# DIGITAL_OUTPUT.net
KiCad netlist of a schematic drawn in Altium Designer
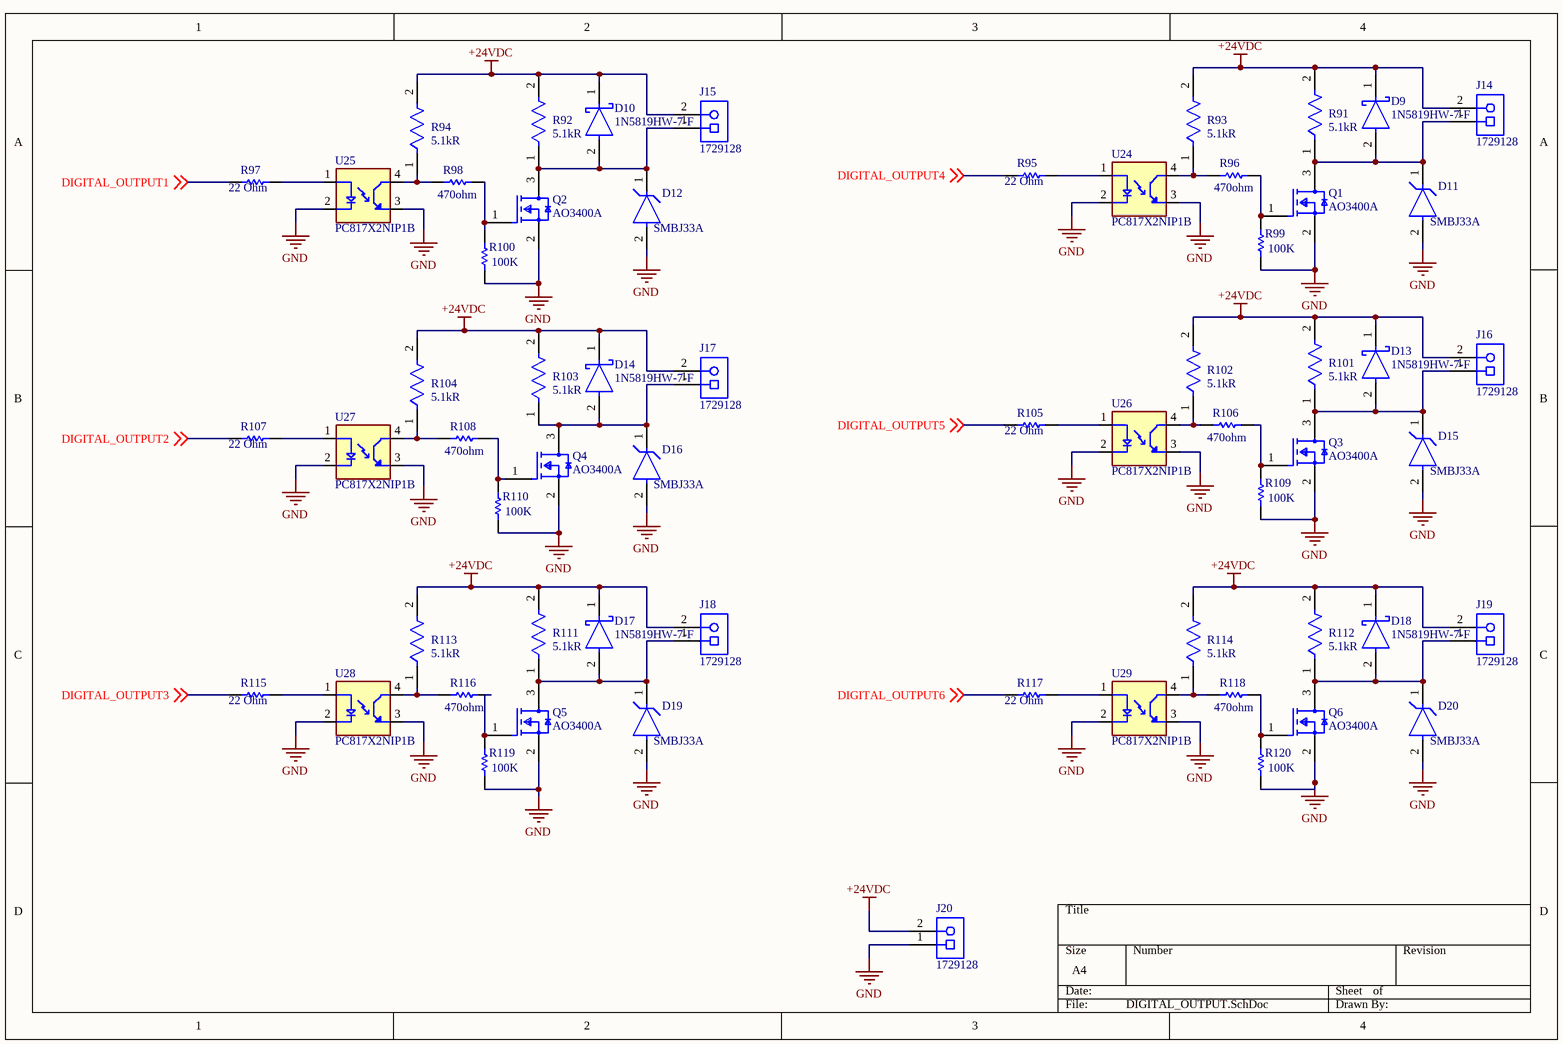
[diagram p0: DIGITAL_OUTPUT.SchDoc]

(export (version "E")
  (design (tool "Eeschema 10.0.6"))
  (components
    (comp (ref "D9")
      (value "1N5819HW-7-F")
      (footprint "FP-SOD123-IPC_A")
      (description "DIODE SCHOTTKY 40V 1A SOD123")
      (libsource (lib "Altium Content Vault") (part "1d6ec82d83fb6aee721767c19dac4b9"))
    )
    (comp (ref "D10")
      (value "1N5819HW-7-F")
      (footprint "FP-SOD123-IPC_A")
      (description "DIODE SCHOTTKY 40V 1A SOD123")
      (libsource (lib "Altium Content Vault") (part "1d6ec82d83fb6aee721767c19dac4b9"))
    )
    (comp (ref "D11")
      (value "SMBJ33A")
      (footprint "FP-SMBJ-MFG")
      (description "TVS DIODE 33V 53.3V DO214AA")
      (fields
        (field (name "MANUFACTURER") "Littelfuse Inc")
        (field (name "OCTOPART") "https://octopart.com/smbj33a-littelfuse-350829")
      )
      (libsource (lib "Altium Content Vault") (part "f813f71cba58e380607f5dd3caf9714"))
    )
    (comp (ref "D12")
      (value "SMBJ33A")
      (footprint "FP-SMBJ-MFG")
      (description "TVS DIODE 33V 53.3V DO214AA")
      (fields
        (field (name "MANUFACTURER") "Littelfuse Inc")
        (field (name "OCTOPART") "https://octopart.com/smbj33a-littelfuse-350829")
      )
      (libsource (lib "Altium Content Vault") (part "f813f71cba58e380607f5dd3caf9714"))
    )
    (comp (ref "D13")
      (value "1N5819HW-7-F")
      (footprint "FP-SOD123-IPC_A")
      (description "DIODE SCHOTTKY 40V 1A SOD123")
      (libsource (lib "Altium Content Vault") (part "1d6ec82d83fb6aee721767c19dac4b9"))
    )
    (comp (ref "D14")
      (value "1N5819HW-7-F")
      (footprint "FP-SOD123-IPC_A")
      (description "DIODE SCHOTTKY 40V 1A SOD123")
      (libsource (lib "Altium Content Vault") (part "1d6ec82d83fb6aee721767c19dac4b9"))
    )
    (comp (ref "D15")
      (value "SMBJ33A")
      (footprint "FP-SMBJ-MFG")
      (description "TVS DIODE 33V 53.3V DO214AA")
      (fields
        (field (name "MANUFACTURER") "Littelfuse Inc")
        (field (name "OCTOPART") "https://octopart.com/smbj33a-littelfuse-350829")
      )
      (libsource (lib "Altium Content Vault") (part "f813f71cba58e380607f5dd3caf9714"))
    )
    (comp (ref "D16")
      (value "SMBJ33A")
      (footprint "FP-SMBJ-MFG")
      (description "TVS DIODE 33V 53.3V DO214AA")
      (fields
        (field (name "MANUFACTURER") "Littelfuse Inc")
        (field (name "OCTOPART") "https://octopart.com/smbj33a-littelfuse-350829")
      )
      (libsource (lib "Altium Content Vault") (part "f813f71cba58e380607f5dd3caf9714"))
    )
    (comp (ref "D17")
      (value "1N5819HW-7-F")
      (footprint "FP-SOD123-IPC_A")
      (description "DIODE SCHOTTKY 40V 1A SOD123")
      (libsource (lib "Altium Content Vault") (part "1d6ec82d83fb6aee721767c19dac4b9"))
    )
    (comp (ref "D18")
      (value "1N5819HW-7-F")
      (footprint "FP-SOD123-IPC_A")
      (description "DIODE SCHOTTKY 40V 1A SOD123")
      (libsource (lib "Altium Content Vault") (part "1d6ec82d83fb6aee721767c19dac4b9"))
    )
    (comp (ref "D19")
      (value "SMBJ33A")
      (footprint "FP-SMBJ-MFG")
      (description "TVS DIODE 33V 53.3V DO214AA")
      (fields
        (field (name "MANUFACTURER") "Littelfuse Inc")
        (field (name "OCTOPART") "https://octopart.com/smbj33a-littelfuse-350829")
      )
      (libsource (lib "Altium Content Vault") (part "f813f71cba58e380607f5dd3caf9714"))
    )
    (comp (ref "D20")
      (value "SMBJ33A")
      (footprint "FP-SMBJ-MFG")
      (description "TVS DIODE 33V 53.3V DO214AA")
      (fields
        (field (name "MANUFACTURER") "Littelfuse Inc")
        (field (name "OCTOPART") "https://octopart.com/smbj33a-littelfuse-350829")
      )
      (libsource (lib "Altium Content Vault") (part "f813f71cba58e380607f5dd3caf9714"))
    )
    (comp (ref "J14")
      (value "1729128")
      (footprint "PHOE-1729128-2_V")
      (description "PCB Terminal Block, 13.5 A, 400 V, 2-Pin THD, RoHS, Bulk")
      (fields (field (name "MANUFACTURER") "Phoenix Contact"))
      (libsource (lib "Altium Content Vault") (part "CN-2P-F-R2"))
    )
    (comp (ref "J15")
      (value "1729128")
      (footprint "PHOE-1729128-2_V")
      (description "PCB Terminal Block, 13.5 A, 400 V, 2-Pin THD, RoHS, Bulk")
      (fields (field (name "MANUFACTURER") "Phoenix Contact"))
      (libsource (lib "Altium Content Vault") (part "CN-2P-F-R2"))
    )
    (comp (ref "J16")
      (value "1729128")
      (footprint "PHOE-1729128-2_V")
      (description "PCB Terminal Block, 13.5 A, 400 V, 2-Pin THD, RoHS, Bulk")
      (fields (field (name "MANUFACTURER") "Phoenix Contact"))
      (libsource (lib "Altium Content Vault") (part "CN-2P-F-R2"))
    )
    (comp (ref "J17")
      (value "1729128")
      (footprint "PHOE-1729128-2_V")
      (description "PCB Terminal Block, 13.5 A, 400 V, 2-Pin THD, RoHS, Bulk")
      (fields (field (name "MANUFACTURER") "Phoenix Contact"))
      (libsource (lib "Altium Content Vault") (part "CN-2P-F-R2"))
    )
    (comp (ref "J18")
      (value "1729128")
      (footprint "PHOE-1729128-2_V")
      (description "PCB Terminal Block, 13.5 A, 400 V, 2-Pin THD, RoHS, Bulk")
      (fields (field (name "MANUFACTURER") "Phoenix Contact"))
      (libsource (lib "Altium Content Vault") (part "CN-2P-F-R2"))
    )
    (comp (ref "J19")
      (value "1729128")
      (footprint "PHOE-1729128-2_V")
      (description "PCB Terminal Block, 13.5 A, 400 V, 2-Pin THD, RoHS, Bulk")
      (fields (field (name "MANUFACTURER") "Phoenix Contact"))
      (libsource (lib "Altium Content Vault") (part "CN-2P-F-R2"))
    )
    (comp (ref "J20")
      (value "1729128")
      (footprint "PHOE-1729128-2_V")
      (description "PCB Terminal Block, 13.5 A, 400 V, 2-Pin THD, RoHS, Bulk")
      (fields (field (name "MANUFACTURER") "Phoenix Contact"))
      (libsource (lib "Altium Content Vault") (part "CN-2P-F-R2"))
    )
    (comp (ref "Q1")
      (value "AO3400A")
      (footprint "FP-SOT23-MFG")
      (description "MOSFET N-CH 30V 5.7A SOT23")
      (libsource (lib "Altium Content Vault") (part "0a9ea7c96deaaede766a5b531c28de0"))
    )
    (comp (ref "Q2")
      (value "AO3400A")
      (footprint "FP-SOT23-MFG")
      (description "MOSFET N-CH 30V 5.7A SOT23")
      (libsource (lib "Altium Content Vault") (part "0a9ea7c96deaaede766a5b531c28de0"))
    )
    (comp (ref "Q3")
      (value "AO3400A")
      (footprint "FP-SOT23-MFG")
      (description "MOSFET N-CH 30V 5.7A SOT23")
      (libsource (lib "Altium Content Vault") (part "0a9ea7c96deaaede766a5b531c28de0"))
    )
    (comp (ref "Q4")
      (value "AO3400A")
      (footprint "FP-SOT23-MFG")
      (description "MOSFET N-CH 30V 5.7A SOT23")
      (libsource (lib "Altium Content Vault") (part "0a9ea7c96deaaede766a5b531c28de0"))
    )
    (comp (ref "Q5")
      (value "AO3400A")
      (footprint "FP-SOT23-MFG")
      (description "MOSFET N-CH 30V 5.7A SOT23")
      (libsource (lib "Altium Content Vault") (part "0a9ea7c96deaaede766a5b531c28de0"))
    )
    (comp (ref "Q6")
      (value "AO3400A")
      (footprint "FP-SOT23-MFG")
      (description "MOSFET N-CH 30V 5.7A SOT23")
      (libsource (lib "Altium Content Vault") (part "0a9ea7c96deaaede766a5b531c28de0"))
    )
    (comp (ref "R91")
      (value "CRCW06035K10FKEA")
      (footprint "FP-CRCW0603-e3-IPC_C")
      (description "RES Thick Film, 5.1kΩ, 1%, 0.1W, 100ppm/°C, 0603")
      (fields (field (name "TOLERANCE") "1%") (field (name "RESISTANCE") "5.1kR"))
      (libsource (lib "Altium Content Vault") (part "1029c3af85768c4190bb7ad29bc67b5"))
    )
    (comp (ref "R92")
      (value "CRCW06035K10FKEA")
      (footprint "FP-CRCW0603-e3-IPC_C")
      (description "RES Thick Film, 5.1kΩ, 1%, 0.1W, 100ppm/°C, 0603")
      (fields (field (name "TOLERANCE") "1%") (field (name "RESISTANCE") "5.1kR"))
      (libsource (lib "Altium Content Vault") (part "1029c3af85768c4190bb7ad29bc67b5"))
    )
    (comp (ref "R93")
      (value "CRCW06035K10FKEA")
      (footprint "FP-CRCW0603-e3-IPC_C")
      (description "RES Thick Film, 5.1kΩ, 1%, 0.1W, 100ppm/°C, 0603")
      (fields (field (name "TOLERANCE") "1%") (field (name "RESISTANCE") "5.1kR"))
      (libsource (lib "Altium Content Vault") (part "1029c3af85768c4190bb7ad29bc67b5"))
    )
    (comp (ref "R94")
      (value "CRCW06035K10FKEA")
      (footprint "FP-CRCW0603-e3-IPC_C")
      (description "RES Thick Film, 5.1kΩ, 1%, 0.1W, 100ppm/°C, 0603")
      (fields (field (name "TOLERANCE") "1%") (field (name "RESISTANCE") "5.1kR"))
      (libsource (lib "Altium Content Vault") (part "1029c3af85768c4190bb7ad29bc67b5"))
    )
    (comp (ref "R95")
      (value "ERJ-3EKF2200V")
      (footprint "RESC1608X55X30LL15T15")
      (description "Chip Resistor, 220 Ohm, +/- 1%, 0.1 W, -55 to 155 degC, 0603 (1608 Metric), RoHS, Tape and Reel")
      (fields (field (name "RESISTANCE") "22 Ohm") (field (name "TOLERANCE") "1%"))
      (libsource (lib "Altium Content Vault") (part "RES-2"))
    )
    (comp (ref "R96")
      (value "RC0805FR-07470RL")
      (footprint "RESC2013X60X35LL10T20")
      (description "Chip Resistor, 470 Ohm, +/- 1%, 125 mW, -55 to 155 degC, 0805 (2012 Metric), RoHS, Tape and Reel")
      (fields (field (name "MANUFACTURER") "Yageo") (field (name "RESISTANCE") "470ohm"))
      (libsource (lib "Altium Content Vault") (part "RES-2"))
    )
    (comp (ref "R97")
      (value "ERJ-3EKF2200V")
      (footprint "RESC1608X55X30LL15T15")
      (description "Chip Resistor, 220 Ohm, +/- 1%, 0.1 W, -55 to 155 degC, 0603 (1608 Metric), RoHS, Tape and Reel")
      (fields (field (name "RESISTANCE") "22 Ohm") (field (name "TOLERANCE") "1%"))
      (libsource (lib "Altium Content Vault") (part "RES-2"))
    )
    (comp (ref "R98")
      (value "RC0805FR-07470RL")
      (footprint "RESC2013X60X35LL10T20")
      (description "Chip Resistor, 470 Ohm, +/- 1%, 125 mW, -55 to 155 degC, 0805 (2012 Metric), RoHS, Tape and Reel")
      (fields (field (name "MANUFACTURER") "Yageo") (field (name "RESISTANCE") "470ohm"))
      (libsource (lib "Altium Content Vault") (part "RES-2"))
    )
    (comp (ref "R99")
      (value "100K")
      (footprint "RESC2013X50X30ML20T20")
      (fields (field (name "MANUFACTURER") "Vishay Dale") (field (name "PART NUMBER") "CRCW0805100KJNEA"))
      (libsource (lib "Altium Content Vault") (part "RES"))
    )
    (comp (ref "R100")
      (value "100K")
      (footprint "RESC2013X50X30ML20T20")
      (fields (field (name "MANUFACTURER") "Vishay Dale") (field (name "PART NUMBER") "CRCW0805100KJNEA"))
      (libsource (lib "Altium Content Vault") (part "RES"))
    )
    (comp (ref "R101")
      (value "CRCW06035K10FKEA")
      (footprint "FP-CRCW0603-e3-IPC_C")
      (description "RES Thick Film, 5.1kΩ, 1%, 0.1W, 100ppm/°C, 0603")
      (fields (field (name "TOLERANCE") "1%") (field (name "RESISTANCE") "5.1kR"))
      (libsource (lib "Altium Content Vault") (part "1029c3af85768c4190bb7ad29bc67b5"))
    )
    (comp (ref "R102")
      (value "CRCW06035K10FKEA")
      (footprint "FP-CRCW0603-e3-IPC_C")
      (description "RES Thick Film, 5.1kΩ, 1%, 0.1W, 100ppm/°C, 0603")
      (fields (field (name "TOLERANCE") "1%") (field (name "RESISTANCE") "5.1kR"))
      (libsource (lib "Altium Content Vault") (part "1029c3af85768c4190bb7ad29bc67b5"))
    )
    (comp (ref "R103")
      (value "CRCW06035K10FKEA")
      (footprint "FP-CRCW0603-e3-IPC_C")
      (description "RES Thick Film, 5.1kΩ, 1%, 0.1W, 100ppm/°C, 0603")
      (fields (field (name "TOLERANCE") "1%") (field (name "RESISTANCE") "5.1kR"))
      (libsource (lib "Altium Content Vault") (part "1029c3af85768c4190bb7ad29bc67b5"))
    )
    (comp (ref "R104")
      (value "CRCW06035K10FKEA")
      (footprint "FP-CRCW0603-e3-IPC_C")
      (description "RES Thick Film, 5.1kΩ, 1%, 0.1W, 100ppm/°C, 0603")
      (fields (field (name "TOLERANCE") "1%") (field (name "RESISTANCE") "5.1kR"))
      (libsource (lib "Altium Content Vault") (part "1029c3af85768c4190bb7ad29bc67b5"))
    )
    (comp (ref "R105")
      (value "ERJ-3EKF2200V")
      (footprint "RESC1608X55X30LL15T15")
      (description "Chip Resistor, 220 Ohm, +/- 1%, 0.1 W, -55 to 155 degC, 0603 (1608 Metric), RoHS, Tape and Reel")
      (fields (field (name "RESISTANCE") "22 Ohm") (field (name "TOLERANCE") "1%"))
      (libsource (lib "Altium Content Vault") (part "RES-2"))
    )
    (comp (ref "R106")
      (value "RC0805FR-07470RL")
      (footprint "RESC2013X60X35LL10T20")
      (description "Chip Resistor, 470 Ohm, +/- 1%, 125 mW, -55 to 155 degC, 0805 (2012 Metric), RoHS, Tape and Reel")
      (fields (field (name "MANUFACTURER") "Yageo") (field (name "RESISTANCE") "470ohm"))
      (libsource (lib "Altium Content Vault") (part "RES-2"))
    )
    (comp (ref "R107")
      (value "ERJ-3EKF2200V")
      (footprint "RESC1608X55X30LL15T15")
      (description "Chip Resistor, 220 Ohm, +/- 1%, 0.1 W, -55 to 155 degC, 0603 (1608 Metric), RoHS, Tape and Reel")
      (fields (field (name "RESISTANCE") "22 Ohm") (field (name "TOLERANCE") "1%"))
      (libsource (lib "Altium Content Vault") (part "RES-2"))
    )
    (comp (ref "R108")
      (value "RC0805FR-07470RL")
      (footprint "RESC2013X60X35LL10T20")
      (description "Chip Resistor, 470 Ohm, +/- 1%, 125 mW, -55 to 155 degC, 0805 (2012 Metric), RoHS, Tape and Reel")
      (fields (field (name "MANUFACTURER") "Yageo") (field (name "RESISTANCE") "470ohm"))
      (libsource (lib "Altium Content Vault") (part "RES-2"))
    )
    (comp (ref "R109")
      (value "100K")
      (footprint "RESC2013X50X30ML20T20")
      (fields (field (name "MANUFACTURER") "Vishay Dale") (field (name "PART NUMBER") "CRCW0805100KJNEA"))
      (libsource (lib "Altium Content Vault") (part "RES"))
    )
    (comp (ref "R110")
      (value "100K")
      (footprint "RESC2013X50X30ML20T20")
      (fields (field (name "MANUFACTURER") "Vishay Dale") (field (name "PART NUMBER") "CRCW0805100KJNEA"))
      (libsource (lib "Altium Content Vault") (part "RES"))
    )
    (comp (ref "R111")
      (value "CRCW06035K10FKEA")
      (footprint "FP-CRCW0603-e3-IPC_C")
      (description "RES Thick Film, 5.1kΩ, 1%, 0.1W, 100ppm/°C, 0603")
      (fields (field (name "TOLERANCE") "1%") (field (name "RESISTANCE") "5.1kR"))
      (libsource (lib "Altium Content Vault") (part "1029c3af85768c4190bb7ad29bc67b5"))
    )
    (comp (ref "R112")
      (value "CRCW06035K10FKEA")
      (footprint "FP-CRCW0603-e3-IPC_C")
      (description "RES Thick Film, 5.1kΩ, 1%, 0.1W, 100ppm/°C, 0603")
      (fields (field (name "TOLERANCE") "1%") (field (name "RESISTANCE") "5.1kR"))
      (libsource (lib "Altium Content Vault") (part "1029c3af85768c4190bb7ad29bc67b5"))
    )
    (comp (ref "R113")
      (value "CRCW06035K10FKEA")
      (footprint "FP-CRCW0603-e3-IPC_C")
      (description "RES Thick Film, 5.1kΩ, 1%, 0.1W, 100ppm/°C, 0603")
      (fields (field (name "TOLERANCE") "1%") (field (name "RESISTANCE") "5.1kR"))
      (libsource (lib "Altium Content Vault") (part "1029c3af85768c4190bb7ad29bc67b5"))
    )
    (comp (ref "R114")
      (value "CRCW06035K10FKEA")
      (footprint "FP-CRCW0603-e3-IPC_C")
      (description "RES Thick Film, 5.1kΩ, 1%, 0.1W, 100ppm/°C, 0603")
      (fields (field (name "TOLERANCE") "1%") (field (name "RESISTANCE") "5.1kR"))
      (libsource (lib "Altium Content Vault") (part "1029c3af85768c4190bb7ad29bc67b5"))
    )
    (comp (ref "R115")
      (value "ERJ-3EKF2200V")
      (footprint "RESC1608X55X30LL15T15")
      (description "Chip Resistor, 220 Ohm, +/- 1%, 0.1 W, -55 to 155 degC, 0603 (1608 Metric), RoHS, Tape and Reel")
      (fields (field (name "RESISTANCE") "22 Ohm") (field (name "TOLERANCE") "1%"))
      (libsource (lib "Altium Content Vault") (part "RES-2"))
    )
    (comp (ref "R116")
      (value "RC0805FR-07470RL")
      (footprint "RESC2013X60X35LL10T20")
      (description "Chip Resistor, 470 Ohm, +/- 1%, 125 mW, -55 to 155 degC, 0805 (2012 Metric), RoHS, Tape and Reel")
      (fields (field (name "MANUFACTURER") "Yageo") (field (name "RESISTANCE") "470ohm"))
      (libsource (lib "Altium Content Vault") (part "RES-2"))
    )
    (comp (ref "R117")
      (value "ERJ-3EKF2200V")
      (footprint "RESC1608X55X30LL15T15")
      (description "Chip Resistor, 220 Ohm, +/- 1%, 0.1 W, -55 to 155 degC, 0603 (1608 Metric), RoHS, Tape and Reel")
      (fields (field (name "RESISTANCE") "22 Ohm") (field (name "TOLERANCE") "1%"))
      (libsource (lib "Altium Content Vault") (part "RES-2"))
    )
    (comp (ref "R118")
      (value "RC0805FR-07470RL")
      (footprint "RESC2013X60X35LL10T20")
      (description "Chip Resistor, 470 Ohm, +/- 1%, 125 mW, -55 to 155 degC, 0805 (2012 Metric), RoHS, Tape and Reel")
      (fields (field (name "MANUFACTURER") "Yageo") (field (name "RESISTANCE") "470ohm"))
      (libsource (lib "Altium Content Vault") (part "RES-2"))
    )
    (comp (ref "R119")
      (value "100K")
      (footprint "RESC2013X50X30ML20T20")
      (fields (field (name "MANUFACTURER") "Vishay Dale") (field (name "PART NUMBER") "CRCW0805100KJNEA"))
      (libsource (lib "Altium Content Vault") (part "RES"))
    )
    (comp (ref "R120")
      (value "100K")
      (footprint "RESC2013X50X30ML20T20")
      (fields (field (name "MANUFACTURER") "Vishay Dale") (field (name "PART NUMBER") "CRCW0805100KJNEA"))
      (libsource (lib "Altium Content Vault") (part "RES"))
    )
    (comp (ref "U24")
      (value "PC817X2NIP1B")
      (footprint "SOIC254P960X420-4N")
      (description "Optocoupler DC-IN 1-CH Transistor DC-OUT 4-Pin DIP SMD T/R")
      (fields (field (name "MF") "Sharp Microelectronics"))
      (libsource (lib "PC817X2NIP1B") (part "PC817X2NIP1B"))
    )
    (comp (ref "U25")
      (value "PC817X2NIP1B")
      (footprint "SOIC254P960X420-4N")
      (description "Optocoupler DC-IN 1-CH Transistor DC-OUT 4-Pin DIP SMD T/R")
      (fields (field (name "MF") "Sharp Microelectronics"))
      (libsource (lib "PC817X2NIP1B") (part "PC817X2NIP1B"))
    )
    (comp (ref "U26")
      (value "PC817X2NIP1B")
      (footprint "SOIC254P960X420-4N")
      (description "Optocoupler DC-IN 1-CH Transistor DC-OUT 4-Pin DIP SMD T/R")
      (fields (field (name "MF") "Sharp Microelectronics"))
      (libsource (lib "PC817X2NIP1B") (part "PC817X2NIP1B"))
    )
    (comp (ref "U27")
      (value "PC817X2NIP1B")
      (footprint "SOIC254P960X420-4N")
      (description "Optocoupler DC-IN 1-CH Transistor DC-OUT 4-Pin DIP SMD T/R")
      (fields (field (name "MF") "Sharp Microelectronics"))
      (libsource (lib "PC817X2NIP1B") (part "PC817X2NIP1B"))
    )
    (comp (ref "U28")
      (value "PC817X2NIP1B")
      (footprint "SOIC254P960X420-4N")
      (description "Optocoupler DC-IN 1-CH Transistor DC-OUT 4-Pin DIP SMD T/R")
      (fields (field (name "MF") "Sharp Microelectronics"))
      (libsource (lib "PC817X2NIP1B") (part "PC817X2NIP1B"))
    )
    (comp (ref "U29")
      (value "PC817X2NIP1B")
      (footprint "SOIC254P960X420-4N")
      (description "Optocoupler DC-IN 1-CH Transistor DC-OUT 4-Pin DIP SMD T/R")
      (fields (field (name "MF") "Sharp Microelectronics"))
      (libsource (lib "PC817X2NIP1B") (part "PC817X2NIP1B"))
    )
  )
  (nets
    (net (code "1") (name "+24VDC") (class "Default")
      (node (ref "D10") (pin "1") (pinfunction "C_1") (pintype "passive"))
      (node (ref "D13") (pin "1") (pinfunction "C_1") (pintype "passive"))
      (node (ref "D14") (pin "1") (pinfunction "C_1") (pintype "passive"))
      (node (ref "D17") (pin "1") (pinfunction "C_1") (pintype "passive"))
      (node (ref "D18") (pin "1") (pinfunction "C_1") (pintype "passive"))
      (node (ref "D9") (pin "1") (pinfunction "C_1") (pintype "passive"))
      (node (ref "J14") (pin "2") (pinfunction "2_2") (pintype "passive"))
      (node (ref "J15") (pin "2") (pinfunction "2_2") (pintype "passive"))
      (node (ref "J16") (pin "2") (pinfunction "2_2") (pintype "passive"))
      (node (ref "J17") (pin "2") (pinfunction "2_2") (pintype "passive"))
      (node (ref "J18") (pin "2") (pinfunction "2_2") (pintype "passive"))
      (node (ref "J19") (pin "2") (pinfunction "2_2") (pintype "passive"))
      (node (ref "J20") (pin "2") (pinfunction "2_2") (pintype "passive"))
      (node (ref "R101") (pin "2") (pinfunction "2_2") (pintype "passive"))
      (node (ref "R102") (pin "2") (pinfunction "2_2") (pintype "passive"))
      (node (ref "R103") (pin "2") (pinfunction "2_2") (pintype "passive"))
      (node (ref "R104") (pin "2") (pinfunction "2_2") (pintype "passive"))
      (node (ref "R111") (pin "2") (pinfunction "2_2") (pintype "passive"))
      (node (ref "R112") (pin "2") (pinfunction "2_2") (pintype "passive"))
      (node (ref "R113") (pin "2") (pinfunction "2_2") (pintype "passive"))
      (node (ref "R114") (pin "2") (pinfunction "2_2") (pintype "passive"))
      (node (ref "R91") (pin "2") (pinfunction "2_2") (pintype "passive"))
      (node (ref "R92") (pin "2") (pinfunction "2_2") (pintype "passive"))
      (node (ref "R93") (pin "2") (pinfunction "2_2") (pintype "passive"))
      (node (ref "R94") (pin "2") (pinfunction "2_2") (pintype "passive"))
    )
    (net (code "2") (name "DIGITAL_OUTPUT1") (class "Default")
      (node (ref "R97") (pin "1") (pinfunction "1_1") (pintype "passive"))
    )
    (net (code "3") (name "DIGITAL_OUTPUT2") (class "Default")
      (node (ref "R107") (pin "1") (pinfunction "1_1") (pintype "passive"))
    )
    (net (code "4") (name "DIGITAL_OUTPUT3") (class "Default")
      (node (ref "R115") (pin "1") (pinfunction "1_1") (pintype "passive"))
    )
    (net (code "5") (name "DIGITAL_OUTPUT4") (class "Default")
      (node (ref "R95") (pin "1") (pinfunction "1_1") (pintype "passive"))
    )
    (net (code "6") (name "DIGITAL_OUTPUT5") (class "Default")
      (node (ref "R105") (pin "1") (pinfunction "1_1") (pintype "passive"))
    )
    (net (code "7") (name "DIGITAL_OUTPUT6") (class "Default")
      (node (ref "R117") (pin "1") (pinfunction "1_1") (pintype "passive"))
    )
    (net (code "8") (name "GND") (class "Default")
      (node (ref "D11") (pin "2") (pinfunction "A_2") (pintype "passive"))
      (node (ref "D12") (pin "2") (pinfunction "A_2") (pintype "passive"))
      (node (ref "D15") (pin "2") (pinfunction "A_2") (pintype "passive"))
      (node (ref "D16") (pin "2") (pinfunction "A_2") (pintype "passive"))
      (node (ref "D19") (pin "2") (pinfunction "A_2") (pintype "passive"))
      (node (ref "D20") (pin "2") (pinfunction "A_2") (pintype "passive"))
      (node (ref "J20") (pin "1") (pinfunction "1_1") (pintype "passive"))
      (node (ref "Q1") (pin "2") (pinfunction "S_2") (pintype "passive"))
      (node (ref "Q2") (pin "2") (pinfunction "S_2") (pintype "passive"))
      (node (ref "Q3") (pin "2") (pinfunction "S_2") (pintype "passive"))
      (node (ref "Q4") (pin "2") (pinfunction "S_2") (pintype "passive"))
      (node (ref "Q5") (pin "2") (pinfunction "S_2") (pintype "passive"))
      (node (ref "Q6") (pin "2") (pinfunction "S_2") (pintype "passive"))
      (node (ref "R100") (pin "1") (pinfunction "1_1") (pintype "passive"))
      (node (ref "R109") (pin "1") (pinfunction "1_1") (pintype "passive"))
      (node (ref "R110") (pin "1") (pinfunction "1_1") (pintype "passive"))
      (node (ref "R119") (pin "1") (pinfunction "1_1") (pintype "passive"))
      (node (ref "R120") (pin "1") (pinfunction "1_1") (pintype "passive"))
      (node (ref "R99") (pin "1") (pinfunction "1_1") (pintype "passive"))
      (node (ref "U24") (pin "2") (pinfunction "C_2") (pintype "passive"))
      (node (ref "U24") (pin "3") (pinfunction "ET_3") (pintype "passive"))
      (node (ref "U25") (pin "2") (pinfunction "C_2") (pintype "passive"))
      (node (ref "U25") (pin "3") (pinfunction "ET_3") (pintype "passive"))
      (node (ref "U26") (pin "2") (pinfunction "C_2") (pintype "passive"))
      (node (ref "U26") (pin "3") (pinfunction "ET_3") (pintype "passive"))
      (node (ref "U27") (pin "2") (pinfunction "C_2") (pintype "passive"))
      (node (ref "U27") (pin "3") (pinfunction "ET_3") (pintype "passive"))
      (node (ref "U28") (pin "2") (pinfunction "C_2") (pintype "passive"))
      (node (ref "U28") (pin "3") (pinfunction "ET_3") (pintype "passive"))
      (node (ref "U29") (pin "2") (pinfunction "C_2") (pintype "passive"))
      (node (ref "U29") (pin "3") (pinfunction "ET_3") (pintype "passive"))
    )
    (net (code "9") (name "Net-(D10-A)") (class "Default")
      (node (ref "D10") (pin "2") (pinfunction "A_2") (pintype "passive"))
      (node (ref "D12") (pin "1") (pinfunction "C_1") (pintype "passive"))
      (node (ref "J15") (pin "1") (pinfunction "1_1") (pintype "passive"))
      (node (ref "Q2") (pin "3") (pinfunction "D_3") (pintype "passive"))
      (node (ref "R92") (pin "1") (pinfunction "1_1") (pintype "passive"))
    )
    (net (code "10") (name "Net-(D11-C)") (class "Default")
      (node (ref "D11") (pin "1") (pinfunction "C_1") (pintype "passive"))
      (node (ref "D9") (pin "2") (pinfunction "A_2") (pintype "passive"))
      (node (ref "J14") (pin "1") (pinfunction "1_1") (pintype "passive"))
      (node (ref "Q1") (pin "3") (pinfunction "D_3") (pintype "passive"))
      (node (ref "R91") (pin "1") (pinfunction "1_1") (pintype "passive"))
    )
    (net (code "11") (name "Net-(D13-A)") (class "Default")
      (node (ref "D13") (pin "2") (pinfunction "A_2") (pintype "passive"))
      (node (ref "D15") (pin "1") (pinfunction "C_1") (pintype "passive"))
      (node (ref "J16") (pin "1") (pinfunction "1_1") (pintype "passive"))
      (node (ref "Q3") (pin "3") (pinfunction "D_3") (pintype "passive"))
      (node (ref "R101") (pin "1") (pinfunction "1_1") (pintype "passive"))
    )
    (net (code "12") (name "Net-(D14-A)") (class "Default")
      (node (ref "D14") (pin "2") (pinfunction "A_2") (pintype "passive"))
      (node (ref "D16") (pin "1") (pinfunction "C_1") (pintype "passive"))
      (node (ref "J17") (pin "1") (pinfunction "1_1") (pintype "passive"))
      (node (ref "Q4") (pin "3") (pinfunction "D_3") (pintype "passive"))
      (node (ref "R103") (pin "1") (pinfunction "1_1") (pintype "passive"))
    )
    (net (code "13") (name "Net-(D17-A)") (class "Default")
      (node (ref "D17") (pin "2") (pinfunction "A_2") (pintype "passive"))
      (node (ref "D19") (pin "1") (pinfunction "C_1") (pintype "passive"))
      (node (ref "J18") (pin "1") (pinfunction "1_1") (pintype "passive"))
      (node (ref "Q5") (pin "3") (pinfunction "D_3") (pintype "passive"))
      (node (ref "R111") (pin "1") (pinfunction "1_1") (pintype "passive"))
    )
    (net (code "14") (name "Net-(D18-A)") (class "Default")
      (node (ref "D18") (pin "2") (pinfunction "A_2") (pintype "passive"))
      (node (ref "D20") (pin "1") (pinfunction "C_1") (pintype "passive"))
      (node (ref "J19") (pin "1") (pinfunction "1_1") (pintype "passive"))
      (node (ref "Q6") (pin "3") (pinfunction "D_3") (pintype "passive"))
      (node (ref "R112") (pin "1") (pinfunction "1_1") (pintype "passive"))
    )
    (net (code "15") (name "Net-(Q1-G)") (class "Default")
      (node (ref "Q1") (pin "1") (pinfunction "G_1") (pintype "passive"))
      (node (ref "R96") (pin "2") (pinfunction "2_2") (pintype "passive"))
      (node (ref "R99") (pin "2") (pinfunction "2_2") (pintype "passive"))
    )
    (net (code "16") (name "Net-(Q2-G)") (class "Default")
      (node (ref "Q2") (pin "1") (pinfunction "G_1") (pintype "passive"))
      (node (ref "R100") (pin "2") (pinfunction "2_2") (pintype "passive"))
      (node (ref "R98") (pin "2") (pinfunction "2_2") (pintype "passive"))
    )
    (net (code "17") (name "Net-(Q3-G)") (class "Default")
      (node (ref "Q3") (pin "1") (pinfunction "G_1") (pintype "passive"))
      (node (ref "R106") (pin "2") (pinfunction "2_2") (pintype "passive"))
      (node (ref "R109") (pin "2") (pinfunction "2_2") (pintype "passive"))
    )
    (net (code "18") (name "Net-(Q4-G)") (class "Default")
      (node (ref "Q4") (pin "1") (pinfunction "G_1") (pintype "passive"))
      (node (ref "R108") (pin "2") (pinfunction "2_2") (pintype "passive"))
      (node (ref "R110") (pin "2") (pinfunction "2_2") (pintype "passive"))
    )
    (net (code "19") (name "Net-(Q5-G)") (class "Default")
      (node (ref "Q5") (pin "1") (pinfunction "G_1") (pintype "passive"))
      (node (ref "R116") (pin "2") (pinfunction "2_2") (pintype "passive"))
      (node (ref "R119") (pin "2") (pinfunction "2_2") (pintype "passive"))
    )
    (net (code "20") (name "Net-(Q6-G)") (class "Default")
      (node (ref "Q6") (pin "1") (pinfunction "G_1") (pintype "passive"))
      (node (ref "R118") (pin "2") (pinfunction "2_2") (pintype "passive"))
      (node (ref "R120") (pin "2") (pinfunction "2_2") (pintype "passive"))
    )
    (net (code "21") (name "Net-(U24-A)") (class "Default")
      (node (ref "R95") (pin "2") (pinfunction "2_2") (pintype "passive"))
      (node (ref "U24") (pin "1") (pinfunction "A_1") (pintype "passive"))
    )
    (net (code "22") (name "Net-(U24-CT)") (class "Default")
      (node (ref "R93") (pin "1") (pinfunction "1_1") (pintype "passive"))
      (node (ref "R96") (pin "1") (pinfunction "1_1") (pintype "passive"))
      (node (ref "U24") (pin "4") (pinfunction "CT_4") (pintype "passive"))
    )
    (net (code "23") (name "Net-(U25-A)") (class "Default")
      (node (ref "R97") (pin "2") (pinfunction "2_2") (pintype "passive"))
      (node (ref "U25") (pin "1") (pinfunction "A_1") (pintype "passive"))
    )
    (net (code "24") (name "Net-(U25-CT)") (class "Default")
      (node (ref "R94") (pin "1") (pinfunction "1_1") (pintype "passive"))
      (node (ref "R98") (pin "1") (pinfunction "1_1") (pintype "passive"))
      (node (ref "U25") (pin "4") (pinfunction "CT_4") (pintype "passive"))
    )
    (net (code "25") (name "Net-(U26-A)") (class "Default")
      (node (ref "R105") (pin "2") (pinfunction "2_2") (pintype "passive"))
      (node (ref "U26") (pin "1") (pinfunction "A_1") (pintype "passive"))
    )
    (net (code "26") (name "Net-(U26-CT)") (class "Default")
      (node (ref "R102") (pin "1") (pinfunction "1_1") (pintype "passive"))
      (node (ref "R106") (pin "1") (pinfunction "1_1") (pintype "passive"))
      (node (ref "U26") (pin "4") (pinfunction "CT_4") (pintype "passive"))
    )
    (net (code "27") (name "Net-(U27-A)") (class "Default")
      (node (ref "R107") (pin "2") (pinfunction "2_2") (pintype "passive"))
      (node (ref "U27") (pin "1") (pinfunction "A_1") (pintype "passive"))
    )
    (net (code "28") (name "Net-(U27-CT)") (class "Default")
      (node (ref "R104") (pin "1") (pinfunction "1_1") (pintype "passive"))
      (node (ref "R108") (pin "1") (pinfunction "1_1") (pintype "passive"))
      (node (ref "U27") (pin "4") (pinfunction "CT_4") (pintype "passive"))
    )
    (net (code "29") (name "Net-(U28-A)") (class "Default")
      (node (ref "R115") (pin "2") (pinfunction "2_2") (pintype "passive"))
      (node (ref "U28") (pin "1") (pinfunction "A_1") (pintype "passive"))
    )
    (net (code "30") (name "Net-(U28-CT)") (class "Default")
      (node (ref "R113") (pin "1") (pinfunction "1_1") (pintype "passive"))
      (node (ref "R116") (pin "1") (pinfunction "1_1") (pintype "passive"))
      (node (ref "U28") (pin "4") (pinfunction "CT_4") (pintype "passive"))
    )
    (net (code "31") (name "Net-(U29-A)") (class "Default")
      (node (ref "R117") (pin "2") (pinfunction "2_2") (pintype "passive"))
      (node (ref "U29") (pin "1") (pinfunction "A_1") (pintype "passive"))
    )
    (net (code "32") (name "Net-(U29-CT)") (class "Default")
      (node (ref "R114") (pin "1") (pinfunction "1_1") (pintype "passive"))
      (node (ref "R118") (pin "1") (pinfunction "1_1") (pintype "passive"))
      (node (ref "U29") (pin "4") (pinfunction "CT_4") (pintype "passive"))
    )
  )
)
